# 2023-08-06_LVMi_Thermistors.net
KiCad netlist of a schematic drawn in EAGLE
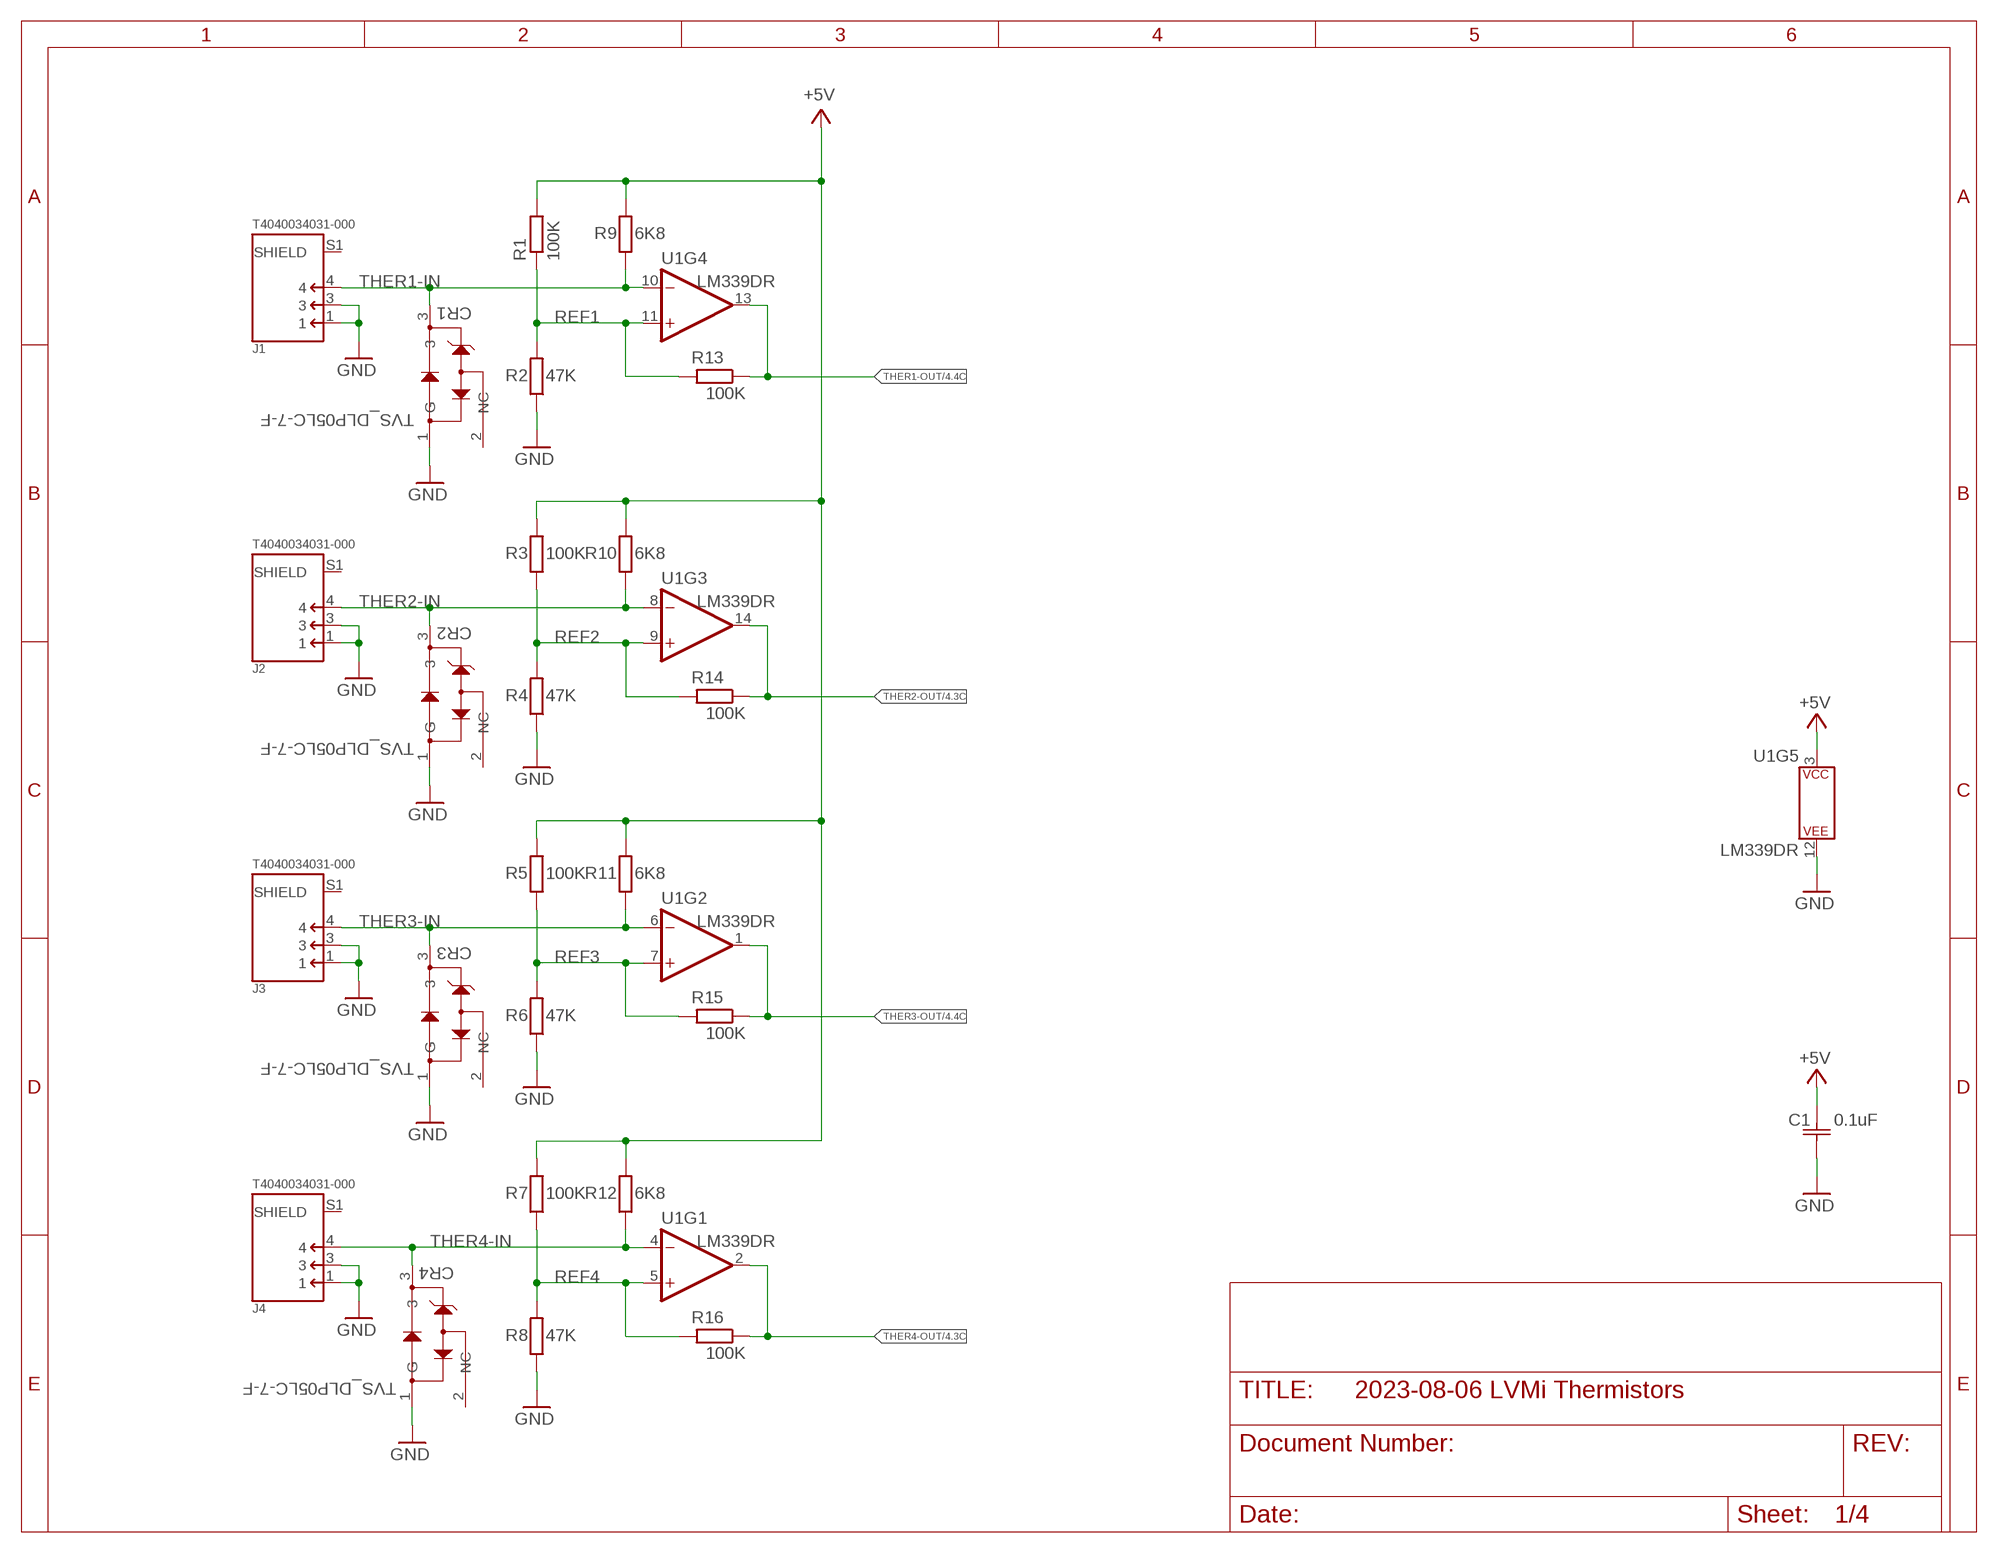
[diagram p0: schematic, sheet 1]
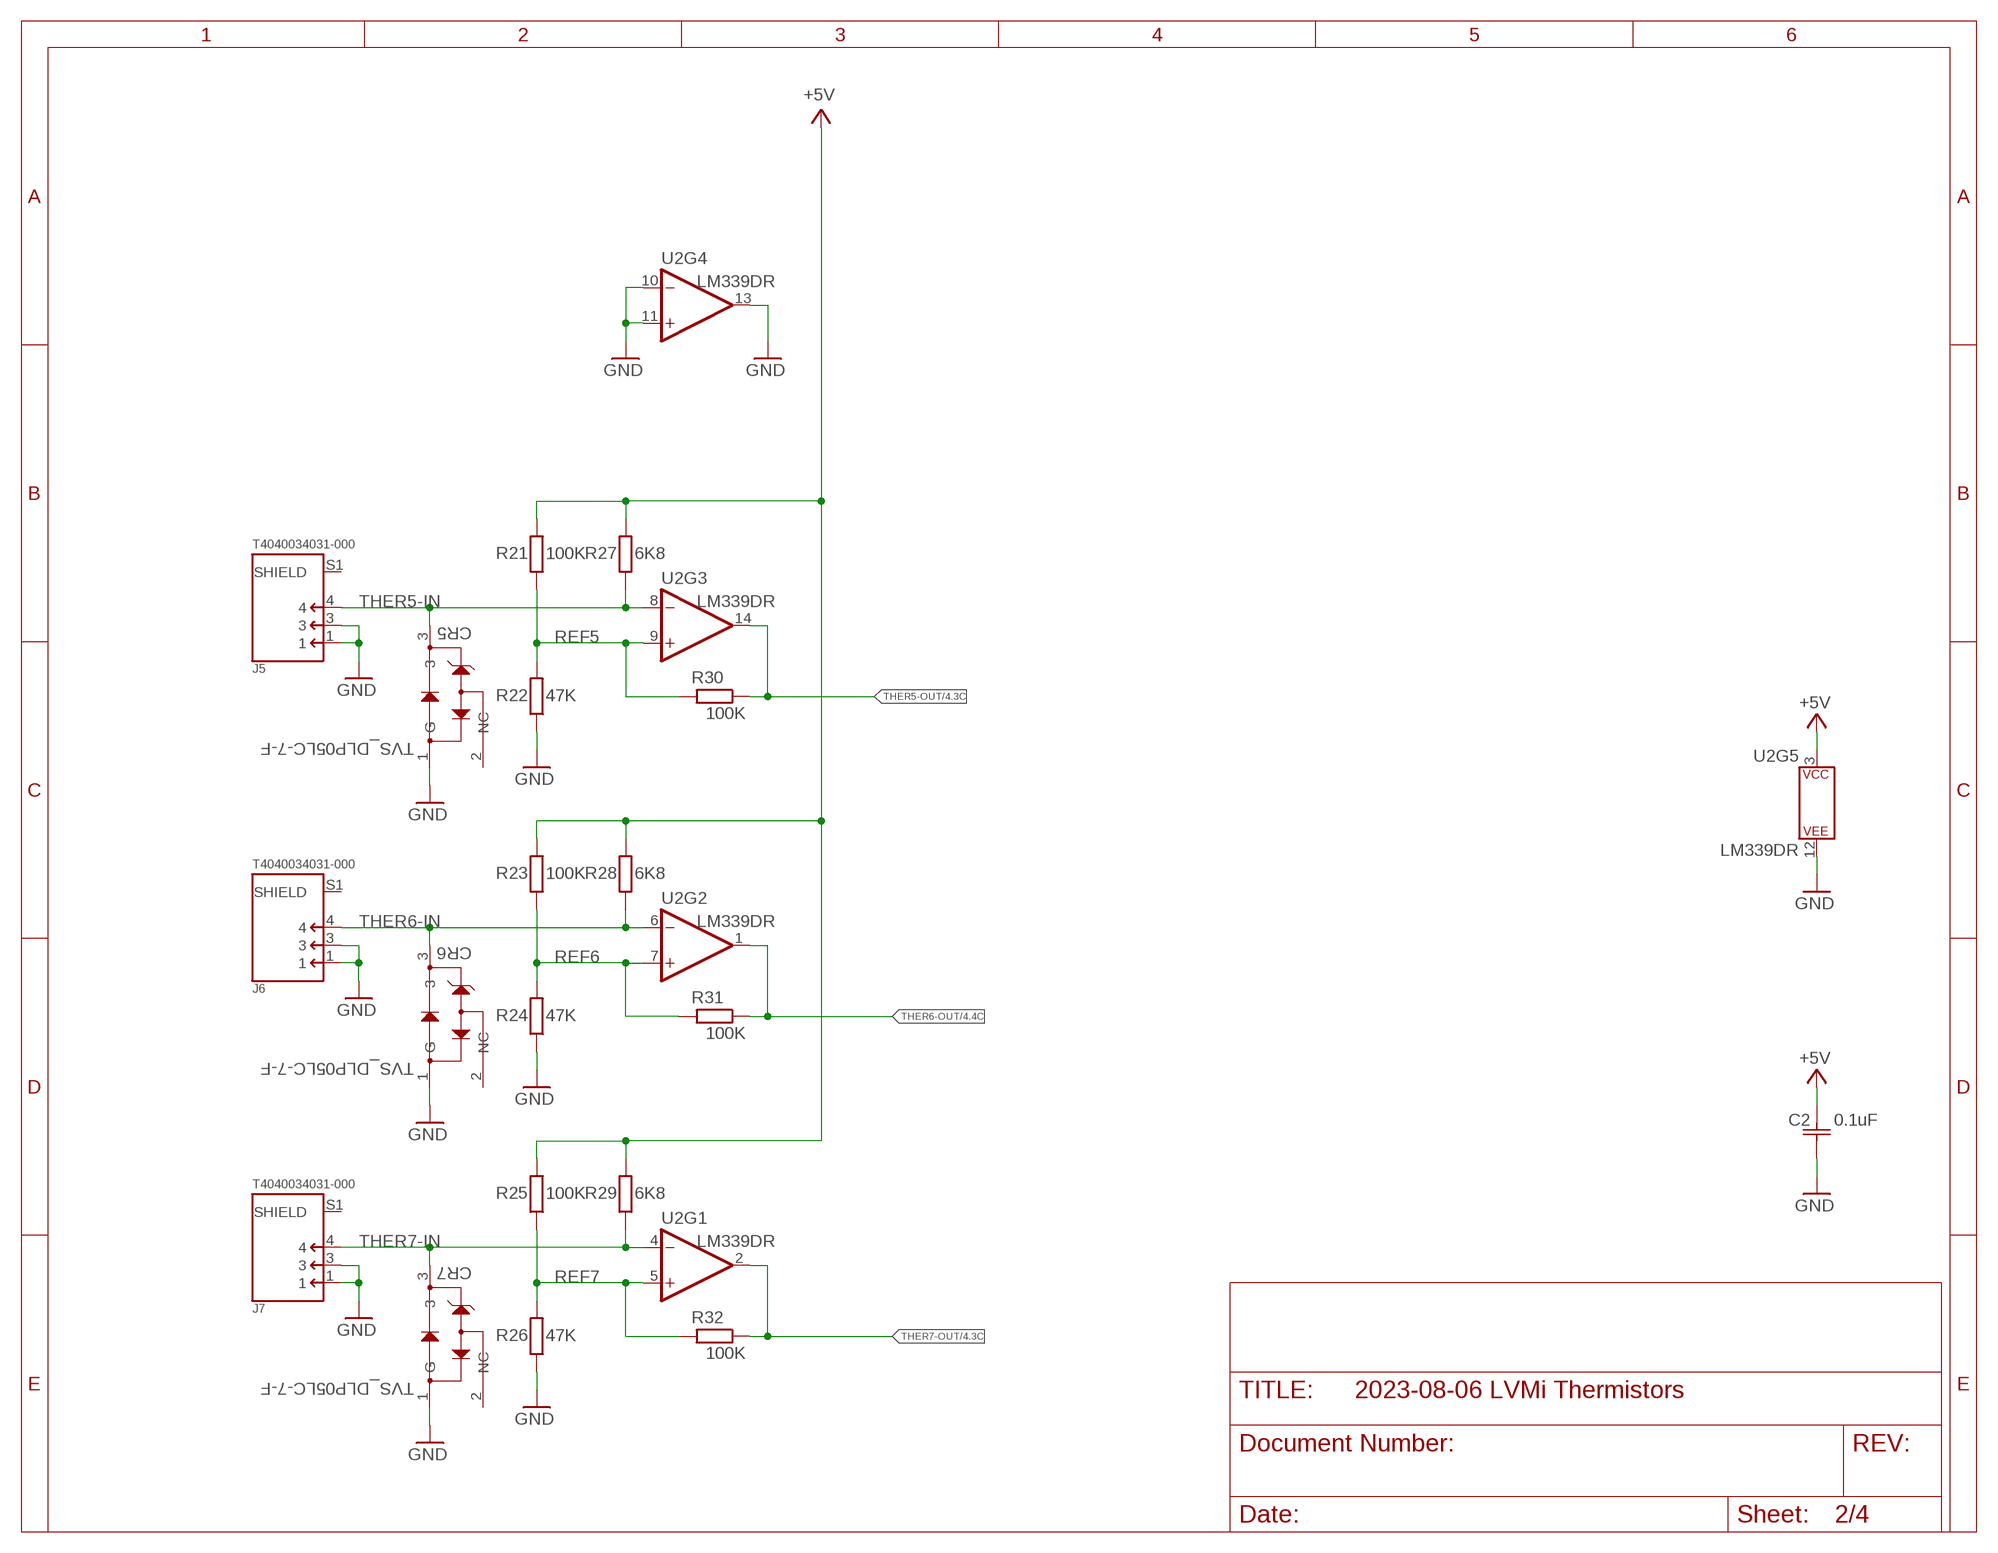
[diagram p1: schematic, sheet 2]
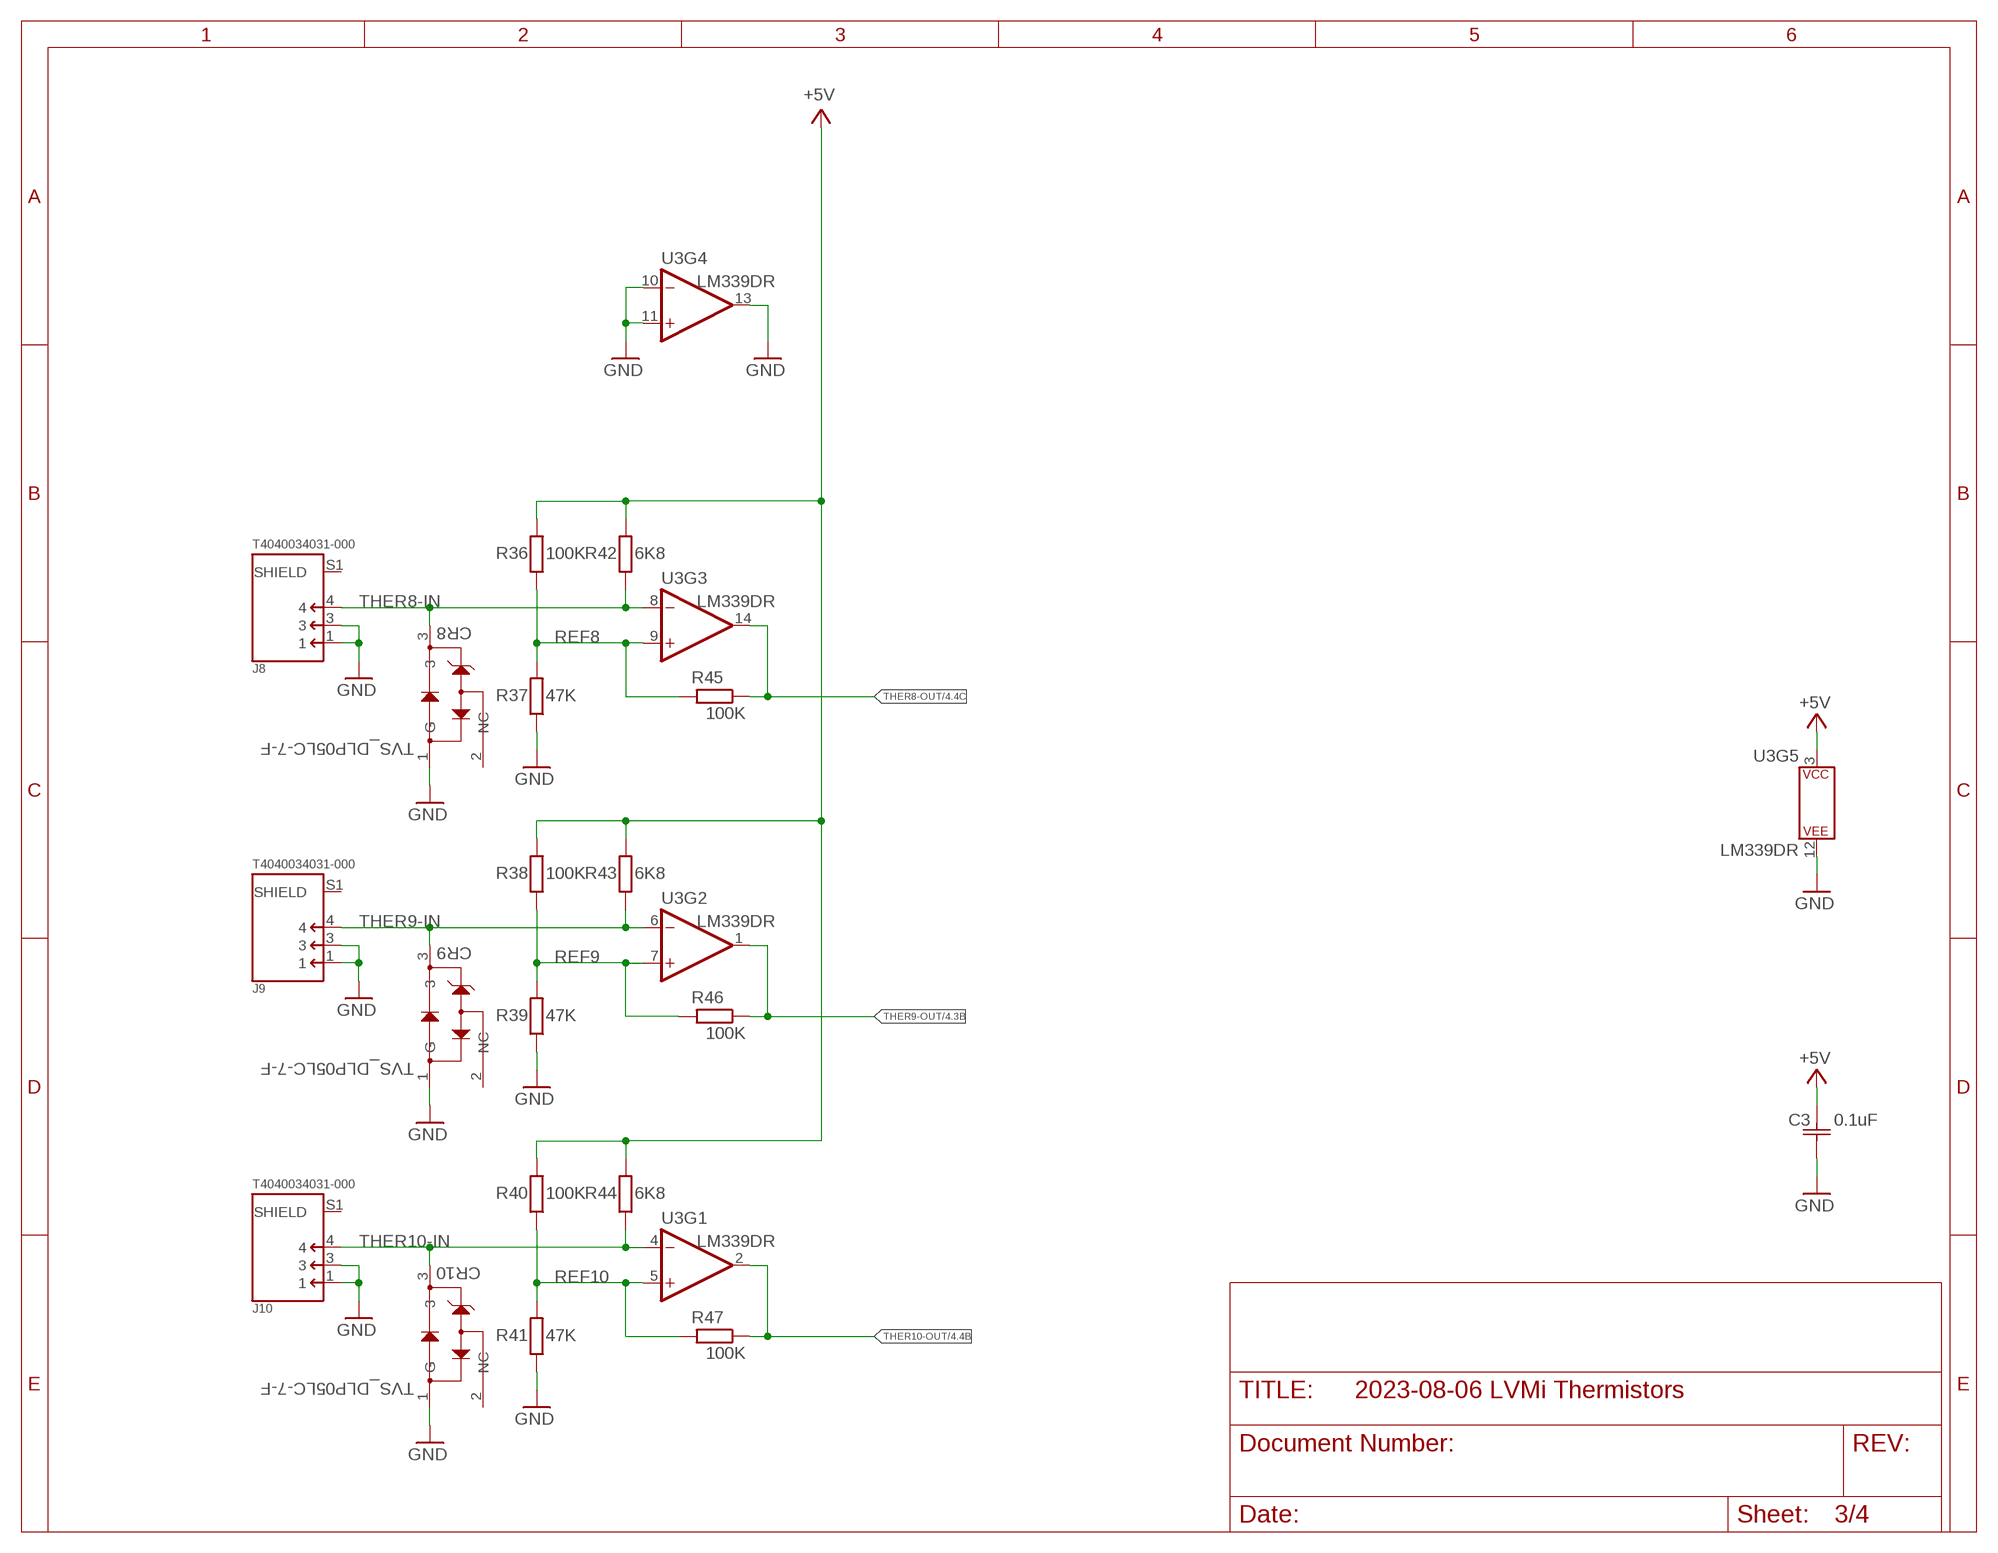
[diagram p2: schematic, sheet 3]
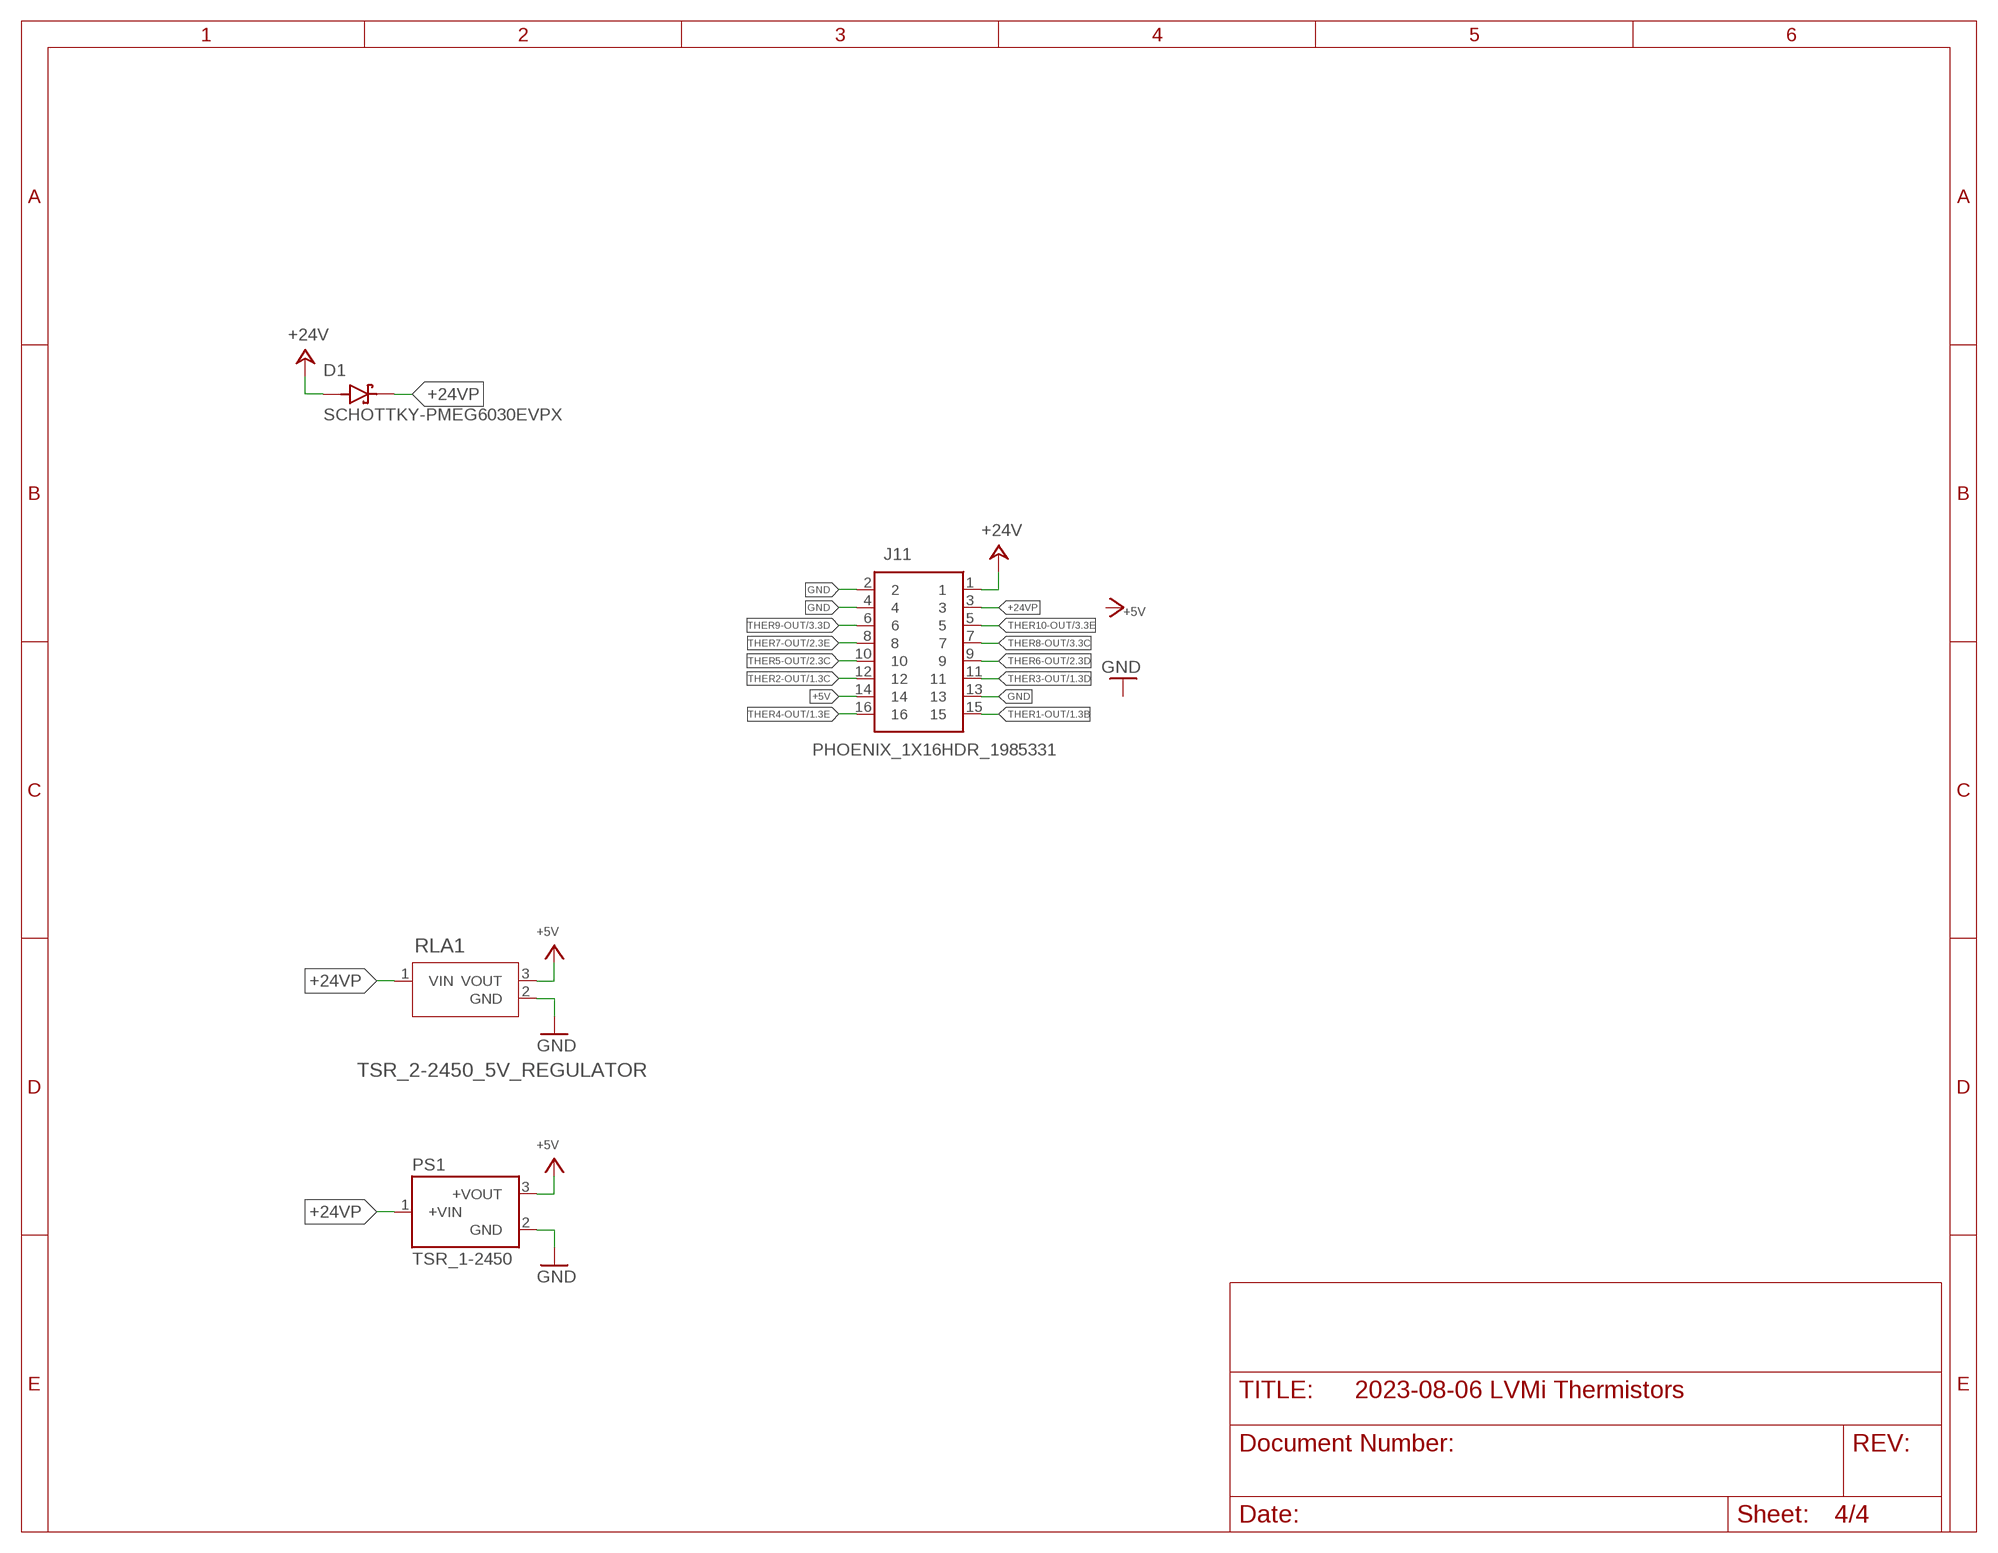
[diagram p3: schematic, sheet 4]

(export (version "E")
  (design (tool "Eeschema 10.0.6"))
  (components
    (comp (ref "C1")
      (value "0.1uF")
      (footprint "eagle-import:K104K15X7RF5TL2_VIS")
      (fields
        (field (name "MANUFACTURER_PART_NUMBER") "K104K15X7RF5TL2")
        (field (name "COPYRIGHT") "Copyright (C) 2023 Ultra Librarian. All rights reserved.")
      )
      (libsource (lib "eagle-import") (part "CAPTHRUHOLE"))
    )
    (comp (ref "CR1")
      (value "TVS_DLP05LC-7-F")
      (footprint "eagle-import:SOT23_DLP05LC_DIO")
      (fields
        (field (name "MANUFACTURER_PART_NUMBER") "DLP05LC-7-F")
        (field (name "COPYRIGHT") "Copyright (C) 2023 Ultra Librarian. All rights reserved.")
      )
      (libsource (lib "eagle-import") (part "TVS_DLP05LC-7-F"))
    )
    (comp (ref "CR2")
      (value "TVS_DLP05LC-7-F")
      (footprint "eagle-import:SOT23_DLP05LC_DIO")
      (fields
        (field (name "MANUFACTURER_PART_NUMBER") "DLP05LC-7-F")
        (field (name "COPYRIGHT") "Copyright (C) 2023 Ultra Librarian. All rights reserved.")
      )
      (libsource (lib "eagle-import") (part "TVS_DLP05LC-7-F"))
    )
    (comp (ref "CR3")
      (value "TVS_DLP05LC-7-F")
      (footprint "eagle-import:SOT23_DLP05LC_DIO")
      (fields
        (field (name "MANUFACTURER_PART_NUMBER") "DLP05LC-7-F")
        (field (name "COPYRIGHT") "Copyright (C) 2023 Ultra Librarian. All rights reserved.")
      )
      (libsource (lib "eagle-import") (part "TVS_DLP05LC-7-F"))
    )
    (comp (ref "CR4")
      (value "TVS_DLP05LC-7-F")
      (footprint "eagle-import:SOT23_DLP05LC_DIO")
      (fields
        (field (name "MANUFACTURER_PART_NUMBER") "DLP05LC-7-F")
        (field (name "COPYRIGHT") "Copyright (C) 2023 Ultra Librarian. All rights reserved.")
      )
      (libsource (lib "eagle-import") (part "TVS_DLP05LC-7-F"))
    )
    (comp (ref "J1")
      (value "T4040034031-000")
      (footprint "eagle-import:TE_T4040034031-000")
      (fields (field (name "MANUFACTURER") "TE "))
      (libsource (lib "eagle-import") (part "T4040034031-000"))
    )
    (comp (ref "J2")
      (value "T4040034031-000")
      (footprint "eagle-import:TE_T4040034031-000")
      (fields (field (name "MANUFACTURER") "TE "))
      (libsource (lib "eagle-import") (part "T4040034031-000"))
    )
    (comp (ref "J3")
      (value "T4040034031-000")
      (footprint "eagle-import:TE_T4040034031-000")
      (fields (field (name "MANUFACTURER") "TE "))
      (libsource (lib "eagle-import") (part "T4040034031-000"))
    )
    (comp (ref "J4")
      (value "T4040034031-000")
      (footprint "eagle-import:TE_T4040034031-000")
      (fields (field (name "MANUFACTURER") "TE "))
      (libsource (lib "eagle-import") (part "T4040034031-000"))
    )
    (comp (ref "R1")
      (value "100K")
      (footprint "eagle-import:0204_7")
      (libsource (lib "eagle-import") (part "R-EU_0204/7"))
    )
    (comp (ref "R2")
      (value "47K")
      (footprint "eagle-import:0204_7")
      (libsource (lib "eagle-import") (part "R-EU_0204/7"))
    )
    (comp (ref "R3")
      (value "100K")
      (footprint "eagle-import:0204_7")
      (libsource (lib "eagle-import") (part "R-EU_0204/7"))
    )
    (comp (ref "R4")
      (value "47K")
      (footprint "eagle-import:0204_7")
      (libsource (lib "eagle-import") (part "R-EU_0204/7"))
    )
    (comp (ref "R5")
      (value "100K")
      (footprint "eagle-import:0204_7")
      (libsource (lib "eagle-import") (part "R-EU_0204/7"))
    )
    (comp (ref "R6")
      (value "47K")
      (footprint "eagle-import:0204_7")
      (libsource (lib "eagle-import") (part "R-EU_0204/7"))
    )
    (comp (ref "R7")
      (value "100K")
      (footprint "eagle-import:0204_7")
      (libsource (lib "eagle-import") (part "R-EU_0204/7"))
    )
    (comp (ref "R8")
      (value "47K")
      (footprint "eagle-import:0204_7")
      (libsource (lib "eagle-import") (part "R-EU_0204/7"))
    )
    (comp (ref "R9")
      (value "6K8")
      (footprint "eagle-import:0204_7")
      (libsource (lib "eagle-import") (part "R-EU_0204/7"))
    )
    (comp (ref "R10")
      (value "6K8")
      (footprint "eagle-import:0204_7")
      (libsource (lib "eagle-import") (part "R-EU_0204/7"))
    )
    (comp (ref "R11")
      (value "6K8")
      (footprint "eagle-import:0204_7")
      (libsource (lib "eagle-import") (part "R-EU_0204/7"))
    )
    (comp (ref "R12")
      (value "6K8")
      (footprint "eagle-import:0204_7")
      (libsource (lib "eagle-import") (part "R-EU_0204/7"))
    )
    (comp (ref "R13")
      (value "100K")
      (footprint "eagle-import:0204_7")
      (libsource (lib "eagle-import") (part "R-EU_0204/7"))
    )
    (comp (ref "R14")
      (value "100K")
      (footprint "eagle-import:0204_7")
      (libsource (lib "eagle-import") (part "R-EU_0204/7"))
    )
    (comp (ref "R15")
      (value "100K")
      (footprint "eagle-import:0204_7")
      (libsource (lib "eagle-import") (part "R-EU_0204/7"))
    )
    (comp (ref "R16")
      (value "100K")
      (footprint "eagle-import:0204_7")
      (libsource (lib "eagle-import") (part "R-EU_0204/7"))
    )
    (comp (ref "U1")
      (value "LM339DR")
      (footprint "eagle-import:SOIC127P599X175-14")
      (libsource (lib "eagle-import") (part "LM339SOIC-14"))
    )
    (comp (ref "C3")
      (value "0.1uF")
      (footprint "eagle-import:K104K15X7RF5TL2_VIS")
      (fields
        (field (name "MANUFACTURER_PART_NUMBER") "K104K15X7RF5TL2")
        (field (name "COPYRIGHT") "Copyright (C) 2023 Ultra Librarian. All rights reserved.")
      )
      (libsource (lib "eagle-import") (part "CAPTHRUHOLE"))
    )
    (comp (ref "CR8")
      (value "TVS_DLP05LC-7-F")
      (footprint "eagle-import:SOT23_DLP05LC_DIO")
      (fields
        (field (name "MANUFACTURER_PART_NUMBER") "DLP05LC-7-F")
        (field (name "COPYRIGHT") "Copyright (C) 2023 Ultra Librarian. All rights reserved.")
      )
      (libsource (lib "eagle-import") (part "TVS_DLP05LC-7-F"))
    )
    (comp (ref "CR9")
      (value "TVS_DLP05LC-7-F")
      (footprint "eagle-import:SOT23_DLP05LC_DIO")
      (fields
        (field (name "MANUFACTURER_PART_NUMBER") "DLP05LC-7-F")
        (field (name "COPYRIGHT") "Copyright (C) 2023 Ultra Librarian. All rights reserved.")
      )
      (libsource (lib "eagle-import") (part "TVS_DLP05LC-7-F"))
    )
    (comp (ref "CR10")
      (value "TVS_DLP05LC-7-F")
      (footprint "eagle-import:SOT23_DLP05LC_DIO")
      (fields
        (field (name "MANUFACTURER_PART_NUMBER") "DLP05LC-7-F")
        (field (name "COPYRIGHT") "Copyright (C) 2023 Ultra Librarian. All rights reserved.")
      )
      (libsource (lib "eagle-import") (part "TVS_DLP05LC-7-F"))
    )
    (comp (ref "J8")
      (value "T4040034031-000")
      (footprint "eagle-import:TE_T4040034031-000")
      (fields (field (name "MANUFACTURER") "TE "))
      (libsource (lib "eagle-import") (part "T4040034031-000"))
    )
    (comp (ref "J9")
      (value "T4040034031-000")
      (footprint "eagle-import:TE_T4040034031-000")
      (fields (field (name "MANUFACTURER") "TE "))
      (libsource (lib "eagle-import") (part "T4040034031-000"))
    )
    (comp (ref "J10")
      (value "T4040034031-000")
      (footprint "eagle-import:TE_T4040034031-000")
      (fields (field (name "MANUFACTURER") "TE "))
      (libsource (lib "eagle-import") (part "T4040034031-000"))
    )
    (comp (ref "R36")
      (value "100K")
      (footprint "eagle-import:0204_7")
      (libsource (lib "eagle-import") (part "R-EU_0204/7"))
    )
    (comp (ref "R37")
      (value "47K")
      (footprint "eagle-import:0204_7")
      (libsource (lib "eagle-import") (part "R-EU_0204/7"))
    )
    (comp (ref "R38")
      (value "100K")
      (footprint "eagle-import:0204_7")
      (libsource (lib "eagle-import") (part "R-EU_0204/7"))
    )
    (comp (ref "R39")
      (value "47K")
      (footprint "eagle-import:0204_7")
      (libsource (lib "eagle-import") (part "R-EU_0204/7"))
    )
    (comp (ref "R40")
      (value "100K")
      (footprint "eagle-import:0204_7")
      (libsource (lib "eagle-import") (part "R-EU_0204/7"))
    )
    (comp (ref "R41")
      (value "47K")
      (footprint "eagle-import:0204_7")
      (libsource (lib "eagle-import") (part "R-EU_0204/7"))
    )
    (comp (ref "R42")
      (value "6K8")
      (footprint "eagle-import:0204_7")
      (libsource (lib "eagle-import") (part "R-EU_0204/7"))
    )
    (comp (ref "R43")
      (value "6K8")
      (footprint "eagle-import:0204_7")
      (libsource (lib "eagle-import") (part "R-EU_0204/7"))
    )
    (comp (ref "R44")
      (value "6K8")
      (footprint "eagle-import:0204_7")
      (libsource (lib "eagle-import") (part "R-EU_0204/7"))
    )
    (comp (ref "R45")
      (value "100K")
      (footprint "eagle-import:0204_7")
      (libsource (lib "eagle-import") (part "R-EU_0204/7"))
    )
    (comp (ref "R46")
      (value "100K")
      (footprint "eagle-import:0204_7")
      (libsource (lib "eagle-import") (part "R-EU_0204/7"))
    )
    (comp (ref "R47")
      (value "100K")
      (footprint "eagle-import:0204_7")
      (libsource (lib "eagle-import") (part "R-EU_0204/7"))
    )
    (comp (ref "U3")
      (value "LM339DR")
      (footprint "eagle-import:SOIC127P599X175-14")
      (libsource (lib "eagle-import") (part "LM339SOIC-14"))
    )
    (comp (ref "D1")
      (value "SCHOTTKY-PMEG6030EVPX")
      (footprint "eagle-import:DIO_PMEG6030EVPX")
      (fields
        (field (name "DIGI-KEY_PART_NUMBER") "1727-1349-1-ND")
        (field (name "MF") "Nexperia USA")
        (field (name "MP") "PMEG6030EVPX")
      )
      (libsource (lib "eagle-import") (part "SCHOTTKY-PMEG6030EVPX"))
    )
    (comp (ref "J11")
      (value "PHOENIX_1X16HDR_1985331")
      (footprint "eagle-import:1985331")
      (fields
        (field (name "MANUFACTURER_PART_NUMBER") "1985331")
        (field (name "MOUSER_PART_NUMBER") "651-1985331")
      )
      (libsource (lib "eagle-import") (part "PHOENIX_1X16HDR_1985331"))
    )
    (comp (ref "PS1")
      (value "TSR_1-2450")
      (footprint "eagle-import:CONV_TSR_1-2450")
      (fields (field (name "MANUFACTURER") "Traco Power"))
      (libsource (lib "eagle-import") (part "TSR_1-2450"))
    )
    (comp (ref "RLA1")
      (value "TSR_2-2450_5V_REGULATOR")
      (footprint "eagle-import:TSR2-SINGLE_TRP")
      (fields
        (field (name "MANUFACTURER_PART_NUMBER") "TSR 2-2450")
        (field (name "COPYRIGHT") "Copyright (C) 2022 Ultra Librarian. All rights reserved.")
      )
      (libsource (lib "eagle-import") (part "TSR_2-2450_5V_REGULATOR"))
    )
    (comp (ref "C2")
      (value "0.1uF")
      (footprint "eagle-import:K104K15X7RF5TL2_VIS")
      (fields
        (field (name "MANUFACTURER_PART_NUMBER") "K104K15X7RF5TL2")
        (field (name "COPYRIGHT") "Copyright (C) 2023 Ultra Librarian. All rights reserved.")
      )
      (libsource (lib "eagle-import") (part "CAPTHRUHOLE"))
    )
    (comp (ref "CR5")
      (value "TVS_DLP05LC-7-F")
      (footprint "eagle-import:SOT23_DLP05LC_DIO")
      (fields
        (field (name "MANUFACTURER_PART_NUMBER") "DLP05LC-7-F")
        (field (name "COPYRIGHT") "Copyright (C) 2023 Ultra Librarian. All rights reserved.")
      )
      (libsource (lib "eagle-import") (part "TVS_DLP05LC-7-F"))
    )
    (comp (ref "CR6")
      (value "TVS_DLP05LC-7-F")
      (footprint "eagle-import:SOT23_DLP05LC_DIO")
      (fields
        (field (name "MANUFACTURER_PART_NUMBER") "DLP05LC-7-F")
        (field (name "COPYRIGHT") "Copyright (C) 2023 Ultra Librarian. All rights reserved.")
      )
      (libsource (lib "eagle-import") (part "TVS_DLP05LC-7-F"))
    )
    (comp (ref "CR7")
      (value "TVS_DLP05LC-7-F")
      (footprint "eagle-import:SOT23_DLP05LC_DIO")
      (fields
        (field (name "MANUFACTURER_PART_NUMBER") "DLP05LC-7-F")
        (field (name "COPYRIGHT") "Copyright (C) 2023 Ultra Librarian. All rights reserved.")
      )
      (libsource (lib "eagle-import") (part "TVS_DLP05LC-7-F"))
    )
    (comp (ref "J5")
      (value "T4040034031-000")
      (footprint "eagle-import:TE_T4040034031-000")
      (fields (field (name "MANUFACTURER") "TE "))
      (libsource (lib "eagle-import") (part "T4040034031-000"))
    )
    (comp (ref "J6")
      (value "T4040034031-000")
      (footprint "eagle-import:TE_T4040034031-000")
      (fields (field (name "MANUFACTURER") "TE "))
      (libsource (lib "eagle-import") (part "T4040034031-000"))
    )
    (comp (ref "J7")
      (value "T4040034031-000")
      (footprint "eagle-import:TE_T4040034031-000")
      (fields (field (name "MANUFACTURER") "TE "))
      (libsource (lib "eagle-import") (part "T4040034031-000"))
    )
    (comp (ref "R21")
      (value "100K")
      (footprint "eagle-import:0204_7")
      (libsource (lib "eagle-import") (part "R-EU_0204/7"))
    )
    (comp (ref "R22")
      (value "47K")
      (footprint "eagle-import:0204_7")
      (libsource (lib "eagle-import") (part "R-EU_0204/7"))
    )
    (comp (ref "R23")
      (value "100K")
      (footprint "eagle-import:0204_7")
      (libsource (lib "eagle-import") (part "R-EU_0204/7"))
    )
    (comp (ref "R24")
      (value "47K")
      (footprint "eagle-import:0204_7")
      (libsource (lib "eagle-import") (part "R-EU_0204/7"))
    )
    (comp (ref "R25")
      (value "100K")
      (footprint "eagle-import:0204_7")
      (libsource (lib "eagle-import") (part "R-EU_0204/7"))
    )
    (comp (ref "R26")
      (value "47K")
      (footprint "eagle-import:0204_7")
      (libsource (lib "eagle-import") (part "R-EU_0204/7"))
    )
    (comp (ref "R27")
      (value "6K8")
      (footprint "eagle-import:0204_7")
      (libsource (lib "eagle-import") (part "R-EU_0204/7"))
    )
    (comp (ref "R28")
      (value "6K8")
      (footprint "eagle-import:0204_7")
      (libsource (lib "eagle-import") (part "R-EU_0204/7"))
    )
    (comp (ref "R29")
      (value "6K8")
      (footprint "eagle-import:0204_7")
      (libsource (lib "eagle-import") (part "R-EU_0204/7"))
    )
    (comp (ref "R30")
      (value "100K")
      (footprint "eagle-import:0204_7")
      (libsource (lib "eagle-import") (part "R-EU_0204/7"))
    )
    (comp (ref "R31")
      (value "100K")
      (footprint "eagle-import:0204_7")
      (libsource (lib "eagle-import") (part "R-EU_0204/7"))
    )
    (comp (ref "R32")
      (value "100K")
      (footprint "eagle-import:0204_7")
      (libsource (lib "eagle-import") (part "R-EU_0204/7"))
    )
    (comp (ref "U2")
      (value "LM339DR")
      (footprint "eagle-import:SOIC127P599X175-14")
      (libsource (lib "eagle-import") (part "LM339SOIC-14"))
    )
  )
  (nets
    (net (code "1") (name "+5V") (class "Default")
      (node (ref "C1") (pin "2") (pinfunction "2_2") (pintype "passive"))
      (node (ref "C2") (pin "2") (pinfunction "2_2") (pintype "passive"))
      (node (ref "C3") (pin "2") (pinfunction "2_2") (pintype "passive"))
      (node (ref "J11") (pin "14") (pinfunction "14_14") (pintype "bidirectional"))
      (node (ref "PS1") (pin "3") (pinfunction "+VOUT_3") (pintype "output"))
      (node (ref "R1") (pin "2") (pinfunction "2_2") (pintype "passive"))
      (node (ref "R10") (pin "2") (pinfunction "2_2") (pintype "passive"))
      (node (ref "R11") (pin "2") (pinfunction "2_2") (pintype "passive"))
      (node (ref "R12") (pin "2") (pinfunction "2_2") (pintype "passive"))
      (node (ref "R21") (pin "2") (pinfunction "2_2") (pintype "passive"))
      (node (ref "R23") (pin "2") (pinfunction "2_2") (pintype "passive"))
      (node (ref "R25") (pin "2") (pinfunction "2_2") (pintype "passive"))
      (node (ref "R27") (pin "2") (pinfunction "2_2") (pintype "passive"))
      (node (ref "R28") (pin "2") (pinfunction "2_2") (pintype "passive"))
      (node (ref "R29") (pin "2") (pinfunction "2_2") (pintype "passive"))
      (node (ref "R3") (pin "2") (pinfunction "2_2") (pintype "passive"))
      (node (ref "R36") (pin "2") (pinfunction "2_2") (pintype "passive"))
      (node (ref "R38") (pin "2") (pinfunction "2_2") (pintype "passive"))
      (node (ref "R40") (pin "2") (pinfunction "2_2") (pintype "passive"))
      (node (ref "R42") (pin "2") (pinfunction "2_2") (pintype "passive"))
      (node (ref "R43") (pin "2") (pinfunction "2_2") (pintype "passive"))
      (node (ref "R44") (pin "2") (pinfunction "2_2") (pintype "passive"))
      (node (ref "R5") (pin "2") (pinfunction "2_2") (pintype "passive"))
      (node (ref "R7") (pin "2") (pinfunction "2_2") (pintype "passive"))
      (node (ref "R9") (pin "2") (pinfunction "2_2") (pintype "passive"))
      (node (ref "RLA1") (pin "3") (pinfunction "VOUT_3") (pintype "passive"))
      (node (ref "U1") (pin "3") (pinfunction "P$V+_3") (pintype "bidirectional"))
      (node (ref "U2") (pin "3") (pinfunction "P$V+_3") (pintype "bidirectional"))
      (node (ref "U3") (pin "3") (pinfunction "P$V+_3") (pintype "bidirectional"))
    )
    (net (code "2") (name "+24V") (class "Default")
      (node (ref "D1") (pin "2") (pinfunction "A_2") (pintype "passive"))
      (node (ref "J11") (pin "1") (pinfunction "1_1") (pintype "bidirectional"))
    )
    (net (code "3") (name "+24VP") (class "Default")
      (node (ref "D1") (pin "1") (pinfunction "K_1") (pintype "passive"))
      (node (ref "J11") (pin "3") (pinfunction "3_3") (pintype "bidirectional"))
      (node (ref "PS1") (pin "1") (pinfunction "+VIN_1") (pintype "input"))
      (node (ref "RLA1") (pin "1") (pinfunction "VIN_1") (pintype "passive"))
    )
    (net (code "4") (name "GND") (class "Default")
      (node (ref "C1") (pin "1") (pinfunction "1_1") (pintype "passive"))
      (node (ref "C2") (pin "1") (pinfunction "1_1") (pintype "passive"))
      (node (ref "C3") (pin "1") (pinfunction "1_1") (pintype "passive"))
      (node (ref "CR1") (pin "1") (pinfunction "G_1") (pintype "passive"))
      (node (ref "CR10") (pin "1") (pinfunction "G_1") (pintype "passive"))
      (node (ref "CR2") (pin "1") (pinfunction "G_1") (pintype "passive"))
      (node (ref "CR3") (pin "1") (pinfunction "G_1") (pintype "passive"))
      (node (ref "CR4") (pin "1") (pinfunction "G_1") (pintype "passive"))
      (node (ref "CR5") (pin "1") (pinfunction "G_1") (pintype "passive"))
      (node (ref "CR6") (pin "1") (pinfunction "G_1") (pintype "passive"))
      (node (ref "CR7") (pin "1") (pinfunction "G_1") (pintype "passive"))
      (node (ref "CR8") (pin "1") (pinfunction "G_1") (pintype "passive"))
      (node (ref "CR9") (pin "1") (pinfunction "G_1") (pintype "passive"))
      (node (ref "J1") (pin "1") (pinfunction "1_1") (pintype "passive"))
      (node (ref "J1") (pin "3") (pinfunction "3_3") (pintype "passive"))
      (node (ref "J10") (pin "1") (pinfunction "1_1") (pintype "passive"))
      (node (ref "J10") (pin "3") (pinfunction "3_3") (pintype "passive"))
      (node (ref "J11") (pin "13") (pinfunction "13_13") (pintype "bidirectional"))
      (node (ref "J11") (pin "2") (pinfunction "2_2") (pintype "bidirectional"))
      (node (ref "J11") (pin "4") (pinfunction "4_4") (pintype "bidirectional"))
      (node (ref "J2") (pin "1") (pinfunction "1_1") (pintype "passive"))
      (node (ref "J2") (pin "3") (pinfunction "3_3") (pintype "passive"))
      (node (ref "J3") (pin "1") (pinfunction "1_1") (pintype "passive"))
      (node (ref "J3") (pin "3") (pinfunction "3_3") (pintype "passive"))
      (node (ref "J4") (pin "1") (pinfunction "1_1") (pintype "passive"))
      (node (ref "J4") (pin "3") (pinfunction "3_3") (pintype "passive"))
      (node (ref "J5") (pin "1") (pinfunction "1_1") (pintype "passive"))
      (node (ref "J5") (pin "3") (pinfunction "3_3") (pintype "passive"))
      (node (ref "J6") (pin "1") (pinfunction "1_1") (pintype "passive"))
      (node (ref "J6") (pin "3") (pinfunction "3_3") (pintype "passive"))
      (node (ref "J7") (pin "1") (pinfunction "1_1") (pintype "passive"))
      (node (ref "J7") (pin "3") (pinfunction "3_3") (pintype "passive"))
      (node (ref "J8") (pin "1") (pinfunction "1_1") (pintype "passive"))
      (node (ref "J8") (pin "3") (pinfunction "3_3") (pintype "passive"))
      (node (ref "J9") (pin "1") (pinfunction "1_1") (pintype "passive"))
      (node (ref "J9") (pin "3") (pinfunction "3_3") (pintype "passive"))
      (node (ref "PS1") (pin "2") (pinfunction "GND_2") (pintype "power_in"))
      (node (ref "R2") (pin "1") (pinfunction "1_1") (pintype "passive"))
      (node (ref "R22") (pin "1") (pinfunction "1_1") (pintype "passive"))
      (node (ref "R24") (pin "1") (pinfunction "1_1") (pintype "passive"))
      (node (ref "R26") (pin "1") (pinfunction "1_1") (pintype "passive"))
      (node (ref "R37") (pin "1") (pinfunction "1_1") (pintype "passive"))
      (node (ref "R39") (pin "1") (pinfunction "1_1") (pintype "passive"))
      (node (ref "R4") (pin "1") (pinfunction "1_1") (pintype "passive"))
      (node (ref "R41") (pin "1") (pinfunction "1_1") (pintype "passive"))
      (node (ref "R6") (pin "1") (pinfunction "1_1") (pintype "passive"))
      (node (ref "R8") (pin "1") (pinfunction "1_1") (pintype "passive"))
      (node (ref "RLA1") (pin "2") (pinfunction "GND_2") (pintype "passive"))
      (node (ref "U1") (pin "12") (pinfunction "P$V-_12") (pintype "bidirectional"))
      (node (ref "U2") (pin "10") (pinfunction "-IN_10") (pintype "input"))
      (node (ref "U2") (pin "11") (pinfunction "+IN_11") (pintype "input"))
      (node (ref "U2") (pin "12") (pinfunction "P$V-_12") (pintype "bidirectional"))
      (node (ref "U2") (pin "13") (pinfunction "OUT_13") (pintype "output"))
      (node (ref "U3") (pin "10") (pinfunction "-IN_10") (pintype "input"))
      (node (ref "U3") (pin "11") (pinfunction "+IN_11") (pintype "input"))
      (node (ref "U3") (pin "12") (pinfunction "P$V-_12") (pintype "bidirectional"))
      (node (ref "U3") (pin "13") (pinfunction "OUT_13") (pintype "output"))
    )
    (net (code "5") (name "REF1") (class "Default")
      (node (ref "R1") (pin "1") (pinfunction "1_1") (pintype "passive"))
      (node (ref "R13") (pin "2") (pinfunction "2_2") (pintype "passive"))
      (node (ref "R2") (pin "2") (pinfunction "2_2") (pintype "passive"))
      (node (ref "U1") (pin "11") (pinfunction "+IN_11") (pintype "input"))
    )
    (net (code "6") (name "REF2") (class "Default")
      (node (ref "R14") (pin "2") (pinfunction "2_2") (pintype "passive"))
      (node (ref "R3") (pin "1") (pinfunction "1_1") (pintype "passive"))
      (node (ref "R4") (pin "2") (pinfunction "2_2") (pintype "passive"))
      (node (ref "U1") (pin "9") (pinfunction "+IN_9") (pintype "input"))
    )
    (net (code "7") (name "REF3") (class "Default")
      (node (ref "R15") (pin "2") (pinfunction "2_2") (pintype "passive"))
      (node (ref "R5") (pin "1") (pinfunction "1_1") (pintype "passive"))
      (node (ref "R6") (pin "2") (pinfunction "2_2") (pintype "passive"))
      (node (ref "U1") (pin "7") (pinfunction "+IN_7") (pintype "input"))
    )
    (net (code "8") (name "REF4") (class "Default")
      (node (ref "R16") (pin "2") (pinfunction "2_2") (pintype "passive"))
      (node (ref "R7") (pin "1") (pinfunction "1_1") (pintype "passive"))
      (node (ref "R8") (pin "2") (pinfunction "2_2") (pintype "passive"))
      (node (ref "U1") (pin "5") (pinfunction "+IN_5") (pintype "input"))
    )
    (net (code "9") (name "REF5") (class "Default")
      (node (ref "R21") (pin "1") (pinfunction "1_1") (pintype "passive"))
      (node (ref "R22") (pin "2") (pinfunction "2_2") (pintype "passive"))
      (node (ref "R30") (pin "2") (pinfunction "2_2") (pintype "passive"))
      (node (ref "U2") (pin "9") (pinfunction "+IN_9") (pintype "input"))
    )
    (net (code "10") (name "REF6") (class "Default")
      (node (ref "R23") (pin "1") (pinfunction "1_1") (pintype "passive"))
      (node (ref "R24") (pin "2") (pinfunction "2_2") (pintype "passive"))
      (node (ref "R31") (pin "2") (pinfunction "2_2") (pintype "passive"))
      (node (ref "U2") (pin "7") (pinfunction "+IN_7") (pintype "input"))
    )
    (net (code "11") (name "REF7") (class "Default")
      (node (ref "R25") (pin "1") (pinfunction "1_1") (pintype "passive"))
      (node (ref "R26") (pin "2") (pinfunction "2_2") (pintype "passive"))
      (node (ref "R32") (pin "2") (pinfunction "2_2") (pintype "passive"))
      (node (ref "U2") (pin "5") (pinfunction "+IN_5") (pintype "input"))
    )
    (net (code "12") (name "REF8") (class "Default")
      (node (ref "R36") (pin "1") (pinfunction "1_1") (pintype "passive"))
      (node (ref "R37") (pin "2") (pinfunction "2_2") (pintype "passive"))
      (node (ref "R45") (pin "2") (pinfunction "2_2") (pintype "passive"))
      (node (ref "U3") (pin "9") (pinfunction "+IN_9") (pintype "input"))
    )
    (net (code "13") (name "REF9") (class "Default")
      (node (ref "R38") (pin "1") (pinfunction "1_1") (pintype "passive"))
      (node (ref "R39") (pin "2") (pinfunction "2_2") (pintype "passive"))
      (node (ref "R46") (pin "2") (pinfunction "2_2") (pintype "passive"))
      (node (ref "U3") (pin "7") (pinfunction "+IN_7") (pintype "input"))
    )
    (net (code "14") (name "REF10") (class "Default")
      (node (ref "R40") (pin "1") (pinfunction "1_1") (pintype "passive"))
      (node (ref "R41") (pin "2") (pinfunction "2_2") (pintype "passive"))
      (node (ref "R47") (pin "2") (pinfunction "2_2") (pintype "passive"))
      (node (ref "U3") (pin "5") (pinfunction "+IN_5") (pintype "input"))
    )
    (net (code "15") (name "THER1-IN") (class "Default")
      (node (ref "CR1") (pin "3") (pinfunction "3_3") (pintype "passive"))
      (node (ref "J1") (pin "4") (pinfunction "4_4") (pintype "passive"))
      (node (ref "R9") (pin "1") (pinfunction "1_1") (pintype "passive"))
      (node (ref "U1") (pin "10") (pinfunction "-IN_10") (pintype "input"))
    )
    (net (code "16") (name "THER1-OUT") (class "Default")
      (node (ref "J11") (pin "15") (pinfunction "15_15") (pintype "bidirectional"))
      (node (ref "R13") (pin "1") (pinfunction "1_1") (pintype "passive"))
      (node (ref "U1") (pin "13") (pinfunction "OUT_13") (pintype "output"))
    )
    (net (code "17") (name "THER2-IN") (class "Default")
      (node (ref "CR2") (pin "3") (pinfunction "3_3") (pintype "passive"))
      (node (ref "J2") (pin "4") (pinfunction "4_4") (pintype "passive"))
      (node (ref "R10") (pin "1") (pinfunction "1_1") (pintype "passive"))
      (node (ref "U1") (pin "8") (pinfunction "-IN_8") (pintype "input"))
    )
    (net (code "18") (name "THER2-OUT") (class "Default")
      (node (ref "J11") (pin "12") (pinfunction "12_12") (pintype "bidirectional"))
      (node (ref "R14") (pin "1") (pinfunction "1_1") (pintype "passive"))
      (node (ref "U1") (pin "14") (pinfunction "OUT_14") (pintype "output"))
    )
    (net (code "19") (name "THER3-IN") (class "Default")
      (node (ref "CR3") (pin "3") (pinfunction "3_3") (pintype "passive"))
      (node (ref "J3") (pin "4") (pinfunction "4_4") (pintype "passive"))
      (node (ref "R11") (pin "1") (pinfunction "1_1") (pintype "passive"))
      (node (ref "U1") (pin "6") (pinfunction "-IN_6") (pintype "input"))
    )
    (net (code "20") (name "THER3-OUT") (class "Default")
      (node (ref "J11") (pin "11") (pinfunction "11_11") (pintype "bidirectional"))
      (node (ref "R15") (pin "1") (pinfunction "1_1") (pintype "passive"))
      (node (ref "U1") (pin "1") (pinfunction "OUT_1") (pintype "output"))
    )
    (net (code "21") (name "THER4-IN") (class "Default")
      (node (ref "CR4") (pin "3") (pinfunction "3_3") (pintype "passive"))
      (node (ref "J4") (pin "4") (pinfunction "4_4") (pintype "passive"))
      (node (ref "R12") (pin "1") (pinfunction "1_1") (pintype "passive"))
      (node (ref "U1") (pin "4") (pinfunction "-IN_4") (pintype "input"))
    )
    (net (code "22") (name "THER4-OUT") (class "Default")
      (node (ref "J11") (pin "16") (pinfunction "16_16") (pintype "bidirectional"))
      (node (ref "R16") (pin "1") (pinfunction "1_1") (pintype "passive"))
      (node (ref "U1") (pin "2") (pinfunction "OUT_2") (pintype "output"))
    )
    (net (code "23") (name "THER5-IN") (class "Default")
      (node (ref "CR5") (pin "3") (pinfunction "3_3") (pintype "passive"))
      (node (ref "J5") (pin "4") (pinfunction "4_4") (pintype "passive"))
      (node (ref "R27") (pin "1") (pinfunction "1_1") (pintype "passive"))
      (node (ref "U2") (pin "8") (pinfunction "-IN_8") (pintype "input"))
    )
    (net (code "24") (name "THER5-OUT") (class "Default")
      (node (ref "J11") (pin "10") (pinfunction "10_10") (pintype "bidirectional"))
      (node (ref "R30") (pin "1") (pinfunction "1_1") (pintype "passive"))
      (node (ref "U2") (pin "14") (pinfunction "OUT_14") (pintype "output"))
    )
    (net (code "25") (name "THER6-IN") (class "Default")
      (node (ref "CR6") (pin "3") (pinfunction "3_3") (pintype "passive"))
      (node (ref "J6") (pin "4") (pinfunction "4_4") (pintype "passive"))
      (node (ref "R28") (pin "1") (pinfunction "1_1") (pintype "passive"))
      (node (ref "U2") (pin "6") (pinfunction "-IN_6") (pintype "input"))
    )
    (net (code "26") (name "THER6-OUT") (class "Default")
      (node (ref "J11") (pin "9") (pinfunction "9_9") (pintype "bidirectional"))
      (node (ref "R31") (pin "1") (pinfunction "1_1") (pintype "passive"))
      (node (ref "U2") (pin "1") (pinfunction "OUT_1") (pintype "output"))
    )
    (net (code "27") (name "THER7-IN") (class "Default")
      (node (ref "CR7") (pin "3") (pinfunction "3_3") (pintype "passive"))
      (node (ref "J7") (pin "4") (pinfunction "4_4") (pintype "passive"))
      (node (ref "R29") (pin "1") (pinfunction "1_1") (pintype "passive"))
      (node (ref "U2") (pin "4") (pinfunction "-IN_4") (pintype "input"))
    )
    (net (code "28") (name "THER7-OUT") (class "Default")
      (node (ref "J11") (pin "8") (pinfunction "8_8") (pintype "bidirectional"))
      (node (ref "R32") (pin "1") (pinfunction "1_1") (pintype "passive"))
      (node (ref "U2") (pin "2") (pinfunction "OUT_2") (pintype "output"))
    )
    (net (code "29") (name "THER8-IN") (class "Default")
      (node (ref "CR8") (pin "3") (pinfunction "3_3") (pintype "passive"))
      (node (ref "J8") (pin "4") (pinfunction "4_4") (pintype "passive"))
      (node (ref "R42") (pin "1") (pinfunction "1_1") (pintype "passive"))
      (node (ref "U3") (pin "8") (pinfunction "-IN_8") (pintype "input"))
    )
    (net (code "30") (name "THER8-OUT") (class "Default")
      (node (ref "J11") (pin "7") (pinfunction "7_7") (pintype "bidirectional"))
      (node (ref "R45") (pin "1") (pinfunction "1_1") (pintype "passive"))
      (node (ref "U3") (pin "14") (pinfunction "OUT_14") (pintype "output"))
    )
    (net (code "31") (name "THER9-IN") (class "Default")
      (node (ref "CR9") (pin "3") (pinfunction "3_3") (pintype "passive"))
      (node (ref "J9") (pin "4") (pinfunction "4_4") (pintype "passive"))
      (node (ref "R43") (pin "1") (pinfunction "1_1") (pintype "passive"))
      (node (ref "U3") (pin "6") (pinfunction "-IN_6") (pintype "input"))
    )
    (net (code "32") (name "THER9-OUT") (class "Default")
      (node (ref "J11") (pin "6") (pinfunction "6_6") (pintype "bidirectional"))
      (node (ref "R46") (pin "1") (pinfunction "1_1") (pintype "passive"))
      (node (ref "U3") (pin "1") (pinfunction "OUT_1") (pintype "output"))
    )
    (net (code "33") (name "THER10-IN") (class "Default")
      (node (ref "CR10") (pin "3") (pinfunction "3_3") (pintype "passive"))
      (node (ref "J10") (pin "4") (pinfunction "4_4") (pintype "passive"))
      (node (ref "R44") (pin "1") (pinfunction "1_1") (pintype "passive"))
      (node (ref "U3") (pin "4") (pinfunction "-IN_4") (pintype "input"))
    )
    (net (code "34") (name "THER10-OUT") (class "Default")
      (node (ref "J11") (pin "5") (pinfunction "5_5") (pintype "bidirectional"))
      (node (ref "R47") (pin "1") (pinfunction "1_1") (pintype "passive"))
      (node (ref "U3") (pin "2") (pinfunction "OUT_2") (pintype "output"))
    )
    (net (code "35") (name "unconnected-(CR1-NC-Pad2)") (class "Default")
      (node (ref "CR1") (pin "2") (pinfunction "NC_2") (pintype "no_connect"))
    )
    (net (code "36") (name "unconnected-(CR2-NC-Pad2)") (class "Default")
      (node (ref "CR2") (pin "2") (pinfunction "NC_2") (pintype "no_connect"))
    )
    (net (code "37") (name "unconnected-(CR3-NC-Pad2)") (class "Default")
      (node (ref "CR3") (pin "2") (pinfunction "NC_2") (pintype "no_connect"))
    )
    (net (code "38") (name "unconnected-(CR4-NC-Pad2)") (class "Default")
      (node (ref "CR4") (pin "2") (pinfunction "NC_2") (pintype "no_connect"))
    )
    (net (code "39") (name "unconnected-(CR5-NC-Pad2)") (class "Default")
      (node (ref "CR5") (pin "2") (pinfunction "NC_2") (pintype "no_connect"))
    )
    (net (code "40") (name "unconnected-(CR6-NC-Pad2)") (class "Default")
      (node (ref "CR6") (pin "2") (pinfunction "NC_2") (pintype "no_connect"))
    )
    (net (code "41") (name "unconnected-(CR7-NC-Pad2)") (class "Default")
      (node (ref "CR7") (pin "2") (pinfunction "NC_2") (pintype "no_connect"))
    )
    (net (code "42") (name "unconnected-(CR8-NC-Pad2)") (class "Default")
      (node (ref "CR8") (pin "2") (pinfunction "NC_2") (pintype "no_connect"))
    )
    (net (code "43") (name "unconnected-(CR9-NC-Pad2)") (class "Default")
      (node (ref "CR9") (pin "2") (pinfunction "NC_2") (pintype "no_connect"))
    )
    (net (code "44") (name "unconnected-(CR10-NC-Pad2)") (class "Default")
      (node (ref "CR10") (pin "2") (pinfunction "NC_2") (pintype "no_connect"))
    )
    (net (code "45") (name "unconnected-(J1-SHIELD-PadS1)") (class "Default")
      (node (ref "J1") (pin "S1") (pinfunction "SHIELD_S1") (pintype "passive"))
    )
    (net (code "46") (name "unconnected-(J2-SHIELD-PadS1)") (class "Default")
      (node (ref "J2") (pin "S1") (pinfunction "SHIELD_S1") (pintype "passive"))
    )
    (net (code "47") (name "unconnected-(J3-SHIELD-PadS1)") (class "Default")
      (node (ref "J3") (pin "S1") (pinfunction "SHIELD_S1") (pintype "passive"))
    )
    (net (code "48") (name "unconnected-(J4-SHIELD-PadS1)") (class "Default")
      (node (ref "J4") (pin "S1") (pinfunction "SHIELD_S1") (pintype "passive"))
    )
    (net (code "49") (name "unconnected-(J5-SHIELD-PadS1)") (class "Default")
      (node (ref "J5") (pin "S1") (pinfunction "SHIELD_S1") (pintype "passive"))
    )
    (net (code "50") (name "unconnected-(J6-SHIELD-PadS1)") (class "Default")
      (node (ref "J6") (pin "S1") (pinfunction "SHIELD_S1") (pintype "passive"))
    )
    (net (code "51") (name "unconnected-(J7-SHIELD-PadS1)") (class "Default")
      (node (ref "J7") (pin "S1") (pinfunction "SHIELD_S1") (pintype "passive"))
    )
    (net (code "52") (name "unconnected-(J8-SHIELD-PadS1)") (class "Default")
      (node (ref "J8") (pin "S1") (pinfunction "SHIELD_S1") (pintype "passive"))
    )
    (net (code "53") (name "unconnected-(J9-SHIELD-PadS1)") (class "Default")
      (node (ref "J9") (pin "S1") (pinfunction "SHIELD_S1") (pintype "passive"))
    )
    (net (code "54") (name "unconnected-(J10-SHIELD-PadS1)") (class "Default")
      (node (ref "J10") (pin "S1") (pinfunction "SHIELD_S1") (pintype "passive"))
    )
  )
)
